# IO_Expandor.net
KiCad netlist of a schematic drawn in Altium Designer
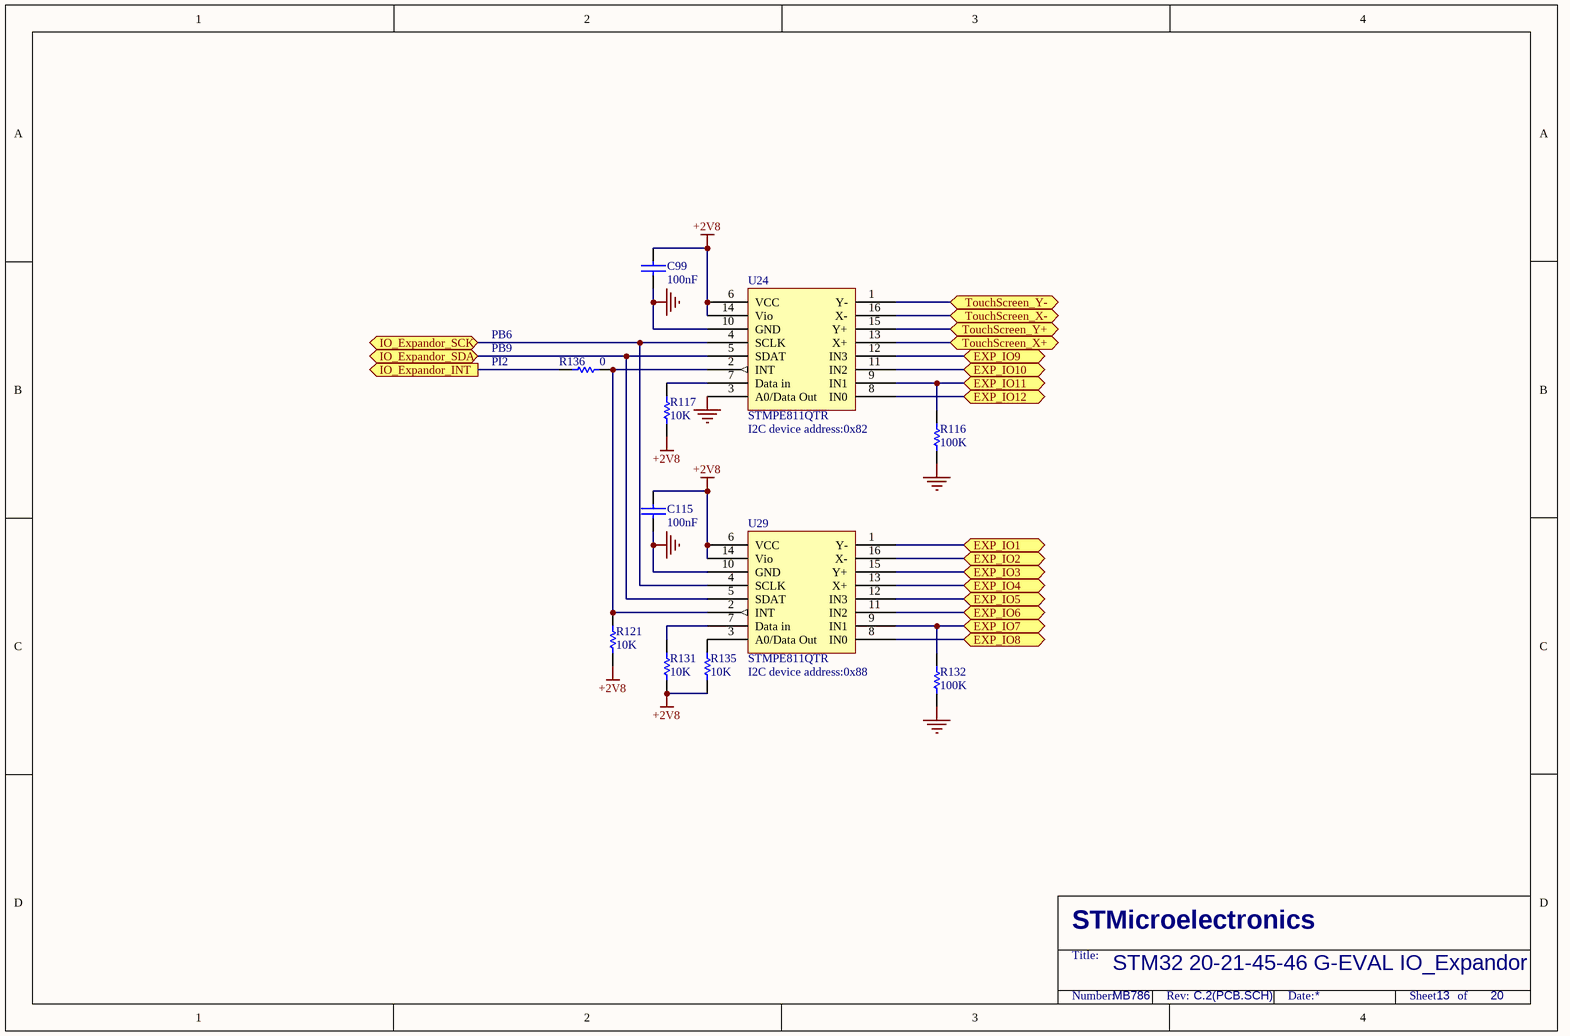
[diagram p0: IO_Expandor.SchDoc]

(export (version "E")
  (design (tool "Eeschema 10.0.6"))
  (components
    (comp (ref "C99")
      (value "100nF")
      (footprint "0402C")
      (description "Capacitor")
      (libsource (lib "*") (part "CAP"))
    )
    (comp (ref "C115")
      (value "100nF")
      (footprint "0402C")
      (description "Capacitor")
      (libsource (lib "*") (part "CAP"))
    )
    (comp (ref "R116")
      (value "100K")
      (footprint "0402R")
      (description "Resistor")
      (fields (field (name "PUBLISHER") "Altium Limited"))
      (libsource (lib "Miscellaneous Devices") (part "Res1"))
    )
    (comp (ref "R117")
      (value "10K")
      (footprint "0402R")
      (description "Resistor")
      (fields (field (name "PUBLISHER") "Altium Limited"))
      (libsource (lib "Miscellaneous Devices") (part "Res1"))
    )
    (comp (ref "R121")
      (value "10K")
      (footprint "0402R")
      (description "Resistor")
      (fields (field (name "PUBLISHER") "Altium Limited"))
      (libsource (lib "Miscellaneous Devices") (part "Res1"))
    )
    (comp (ref "R131")
      (value "10K")
      (footprint "0402R")
      (description "Resistor")
      (fields (field (name "PUBLISHER") "Altium Limited"))
      (libsource (lib "Miscellaneous Devices") (part "Res1"))
    )
    (comp (ref "R132")
      (value "100K")
      (footprint "0402R")
      (description "Resistor")
      (fields (field (name "PUBLISHER") "Altium Limited"))
      (libsource (lib "Miscellaneous Devices") (part "Res1"))
    )
    (comp (ref "R135")
      (value "10K")
      (footprint "0402R")
      (description "Resistor")
      (fields (field (name "PUBLISHER") "Altium Limited"))
      (libsource (lib "Miscellaneous Devices") (part "Res1"))
    )
    (comp (ref "R136")
      (value "0")
      (footprint "0603R")
      (description "Resistor")
      (fields (field (name "PUBLISHER") "Altium Limited"))
      (libsource (lib "Miscellaneous Devices") (part "Res1"))
    )
    (comp (ref "U24")
      (value "STMPE811QTR")
      (footprint "QFN16(3X3)")
      (libsource (lib "MB784") (part "STMPE811"))
    )
    (comp (ref "U29")
      (value "STMPE811QTR")
      (footprint "QFN16(3X3)")
      (libsource (lib "MB784") (part "STMPE811"))
    )
  )
  (nets
    (net (code "1") (name "+2V8") (class "Default")
      (node (ref "C115") (pin "2") (pinfunction "2_2") (pintype "passive"))
      (node (ref "C99") (pin "1") (pinfunction "1_1") (pintype "passive"))
      (node (ref "R117") (pin "2") (pinfunction "2_2") (pintype "passive"))
      (node (ref "R121") (pin "2") (pinfunction "2_2") (pintype "passive"))
      (node (ref "R131") (pin "2") (pinfunction "2_2") (pintype "passive"))
      (node (ref "R135") (pin "2") (pinfunction "2_2") (pintype "passive"))
      (node (ref "U24") (pin "14") (pinfunction "Vio_14") (pintype "passive"))
      (node (ref "U24") (pin "6") (pinfunction "VCC_6") (pintype "passive"))
      (node (ref "U29") (pin "14") (pinfunction "Vio_14") (pintype "passive"))
      (node (ref "U29") (pin "6") (pinfunction "VCC_6") (pintype "passive"))
    )
    (net (code "2") (name "/EXP_IO1") (class "Default")
      (node (ref "U29") (pin "1") (pinfunction "Y-_1") (pintype "passive"))
    )
    (net (code "3") (name "/EXP_IO2") (class "Default")
      (node (ref "U29") (pin "16") (pinfunction "X-_16") (pintype "passive"))
    )
    (net (code "4") (name "/EXP_IO3") (class "Default")
      (node (ref "U29") (pin "15") (pinfunction "Y+_15") (pintype "passive"))
    )
    (net (code "5") (name "/EXP_IO4") (class "Default")
      (node (ref "U29") (pin "13") (pinfunction "X+_13") (pintype "passive"))
    )
    (net (code "6") (name "/EXP_IO5") (class "Default")
      (node (ref "U29") (pin "12") (pinfunction "IN3_12") (pintype "passive"))
    )
    (net (code "7") (name "/EXP_IO6") (class "Default")
      (node (ref "U29") (pin "11") (pinfunction "IN2_11") (pintype "passive"))
    )
    (net (code "8") (name "/EXP_IO7") (class "Default")
      (node (ref "R132") (pin "1") (pinfunction "1_1") (pintype "passive"))
      (node (ref "U29") (pin "9") (pinfunction "IN1_9") (pintype "passive"))
    )
    (net (code "9") (name "/EXP_IO8") (class "Default")
      (node (ref "U29") (pin "8") (pinfunction "IN0_8") (pintype "passive"))
    )
    (net (code "10") (name "/EXP_IO9") (class "Default")
      (node (ref "U24") (pin "12") (pinfunction "IN3_12") (pintype "passive"))
    )
    (net (code "11") (name "/EXP_IO10") (class "Default")
      (node (ref "U24") (pin "11") (pinfunction "IN2_11") (pintype "passive"))
    )
    (net (code "12") (name "/EXP_IO11") (class "Default")
      (node (ref "R116") (pin "1") (pinfunction "1_1") (pintype "passive"))
      (node (ref "U24") (pin "9") (pinfunction "IN1_9") (pintype "passive"))
    )
    (net (code "13") (name "/EXP_IO12") (class "Default")
      (node (ref "U24") (pin "8") (pinfunction "IN0_8") (pintype "passive"))
    )
    (net (code "14") (name "/IO_Expandor_INT") (class "Default")
      (node (ref "R136") (pin "1") (pinfunction "1_1") (pintype "passive"))
    )
    (net (code "15") (name "/IO_Expandor_SCK") (class "Default")
      (node (ref "U24") (pin "4") (pinfunction "SCLK_4") (pintype "passive"))
      (node (ref "U29") (pin "4") (pinfunction "SCLK_4") (pintype "passive"))
    )
    (net (code "16") (name "/IO_Expandor_SDA") (class "Default")
      (node (ref "U24") (pin "5") (pinfunction "SDAT_5") (pintype "passive"))
      (node (ref "U29") (pin "5") (pinfunction "SDAT_5") (pintype "passive"))
    )
    (net (code "17") (name "/TouchScreen_X+") (class "Default")
      (node (ref "U24") (pin "13") (pinfunction "X+_13") (pintype "passive"))
    )
    (net (code "18") (name "/TouchScreen_X-") (class "Default")
      (node (ref "U24") (pin "16") (pinfunction "X-_16") (pintype "passive"))
    )
    (net (code "19") (name "/TouchScreen_Y+") (class "Default")
      (node (ref "U24") (pin "15") (pinfunction "Y+_15") (pintype "passive"))
    )
    (net (code "20") (name "/TouchScreen_Y-") (class "Default")
      (node (ref "U24") (pin "1") (pinfunction "Y-_1") (pintype "passive"))
    )
    (net (code "21") (name "GND") (class "Default")
      (node (ref "C115") (pin "1") (pinfunction "1_1") (pintype "passive"))
      (node (ref "C99") (pin "2") (pinfunction "2_2") (pintype "passive"))
      (node (ref "R116") (pin "2") (pinfunction "2_2") (pintype "passive"))
      (node (ref "R132") (pin "2") (pinfunction "2_2") (pintype "passive"))
      (node (ref "U24") (pin "10") (pinfunction "GND_10") (pintype "passive"))
      (node (ref "U24") (pin "3") (pinfunction "A0/Data_Out_3") (pintype "passive"))
      (node (ref "U29") (pin "10") (pinfunction "GND_10") (pintype "passive"))
    )
    (net (code "22") (name "Net-(U24-Data_in)") (class "Default")
      (node (ref "R117") (pin "1") (pinfunction "1_1") (pintype "passive"))
      (node (ref "U24") (pin "7") (pinfunction "Data_in_7") (pintype "passive"))
    )
    (net (code "23") (name "Net-(U24-INT)") (class "Default")
      (node (ref "R121") (pin "1") (pinfunction "1_1") (pintype "passive"))
      (node (ref "R136") (pin "2") (pinfunction "2_2") (pintype "passive"))
      (node (ref "U24") (pin "2") (pinfunction "INT_2") (pintype "output"))
      (node (ref "U29") (pin "2") (pinfunction "INT_2") (pintype "output"))
    )
    (net (code "24") (name "Net-(U29-A0{slash}Data_Out)") (class "Default")
      (node (ref "R135") (pin "1") (pinfunction "1_1") (pintype "passive"))
      (node (ref "U29") (pin "3") (pinfunction "A0/Data_Out_3") (pintype "passive"))
    )
    (net (code "25") (name "Net-(U29-Data_in)") (class "Default")
      (node (ref "R131") (pin "1") (pinfunction "1_1") (pintype "passive"))
      (node (ref "U29") (pin "7") (pinfunction "Data_in_7") (pintype "passive"))
    )
  )
)
